# knxhome-lqfp32-v3.net
KiCad netlist of a schematic drawn in EAGLE
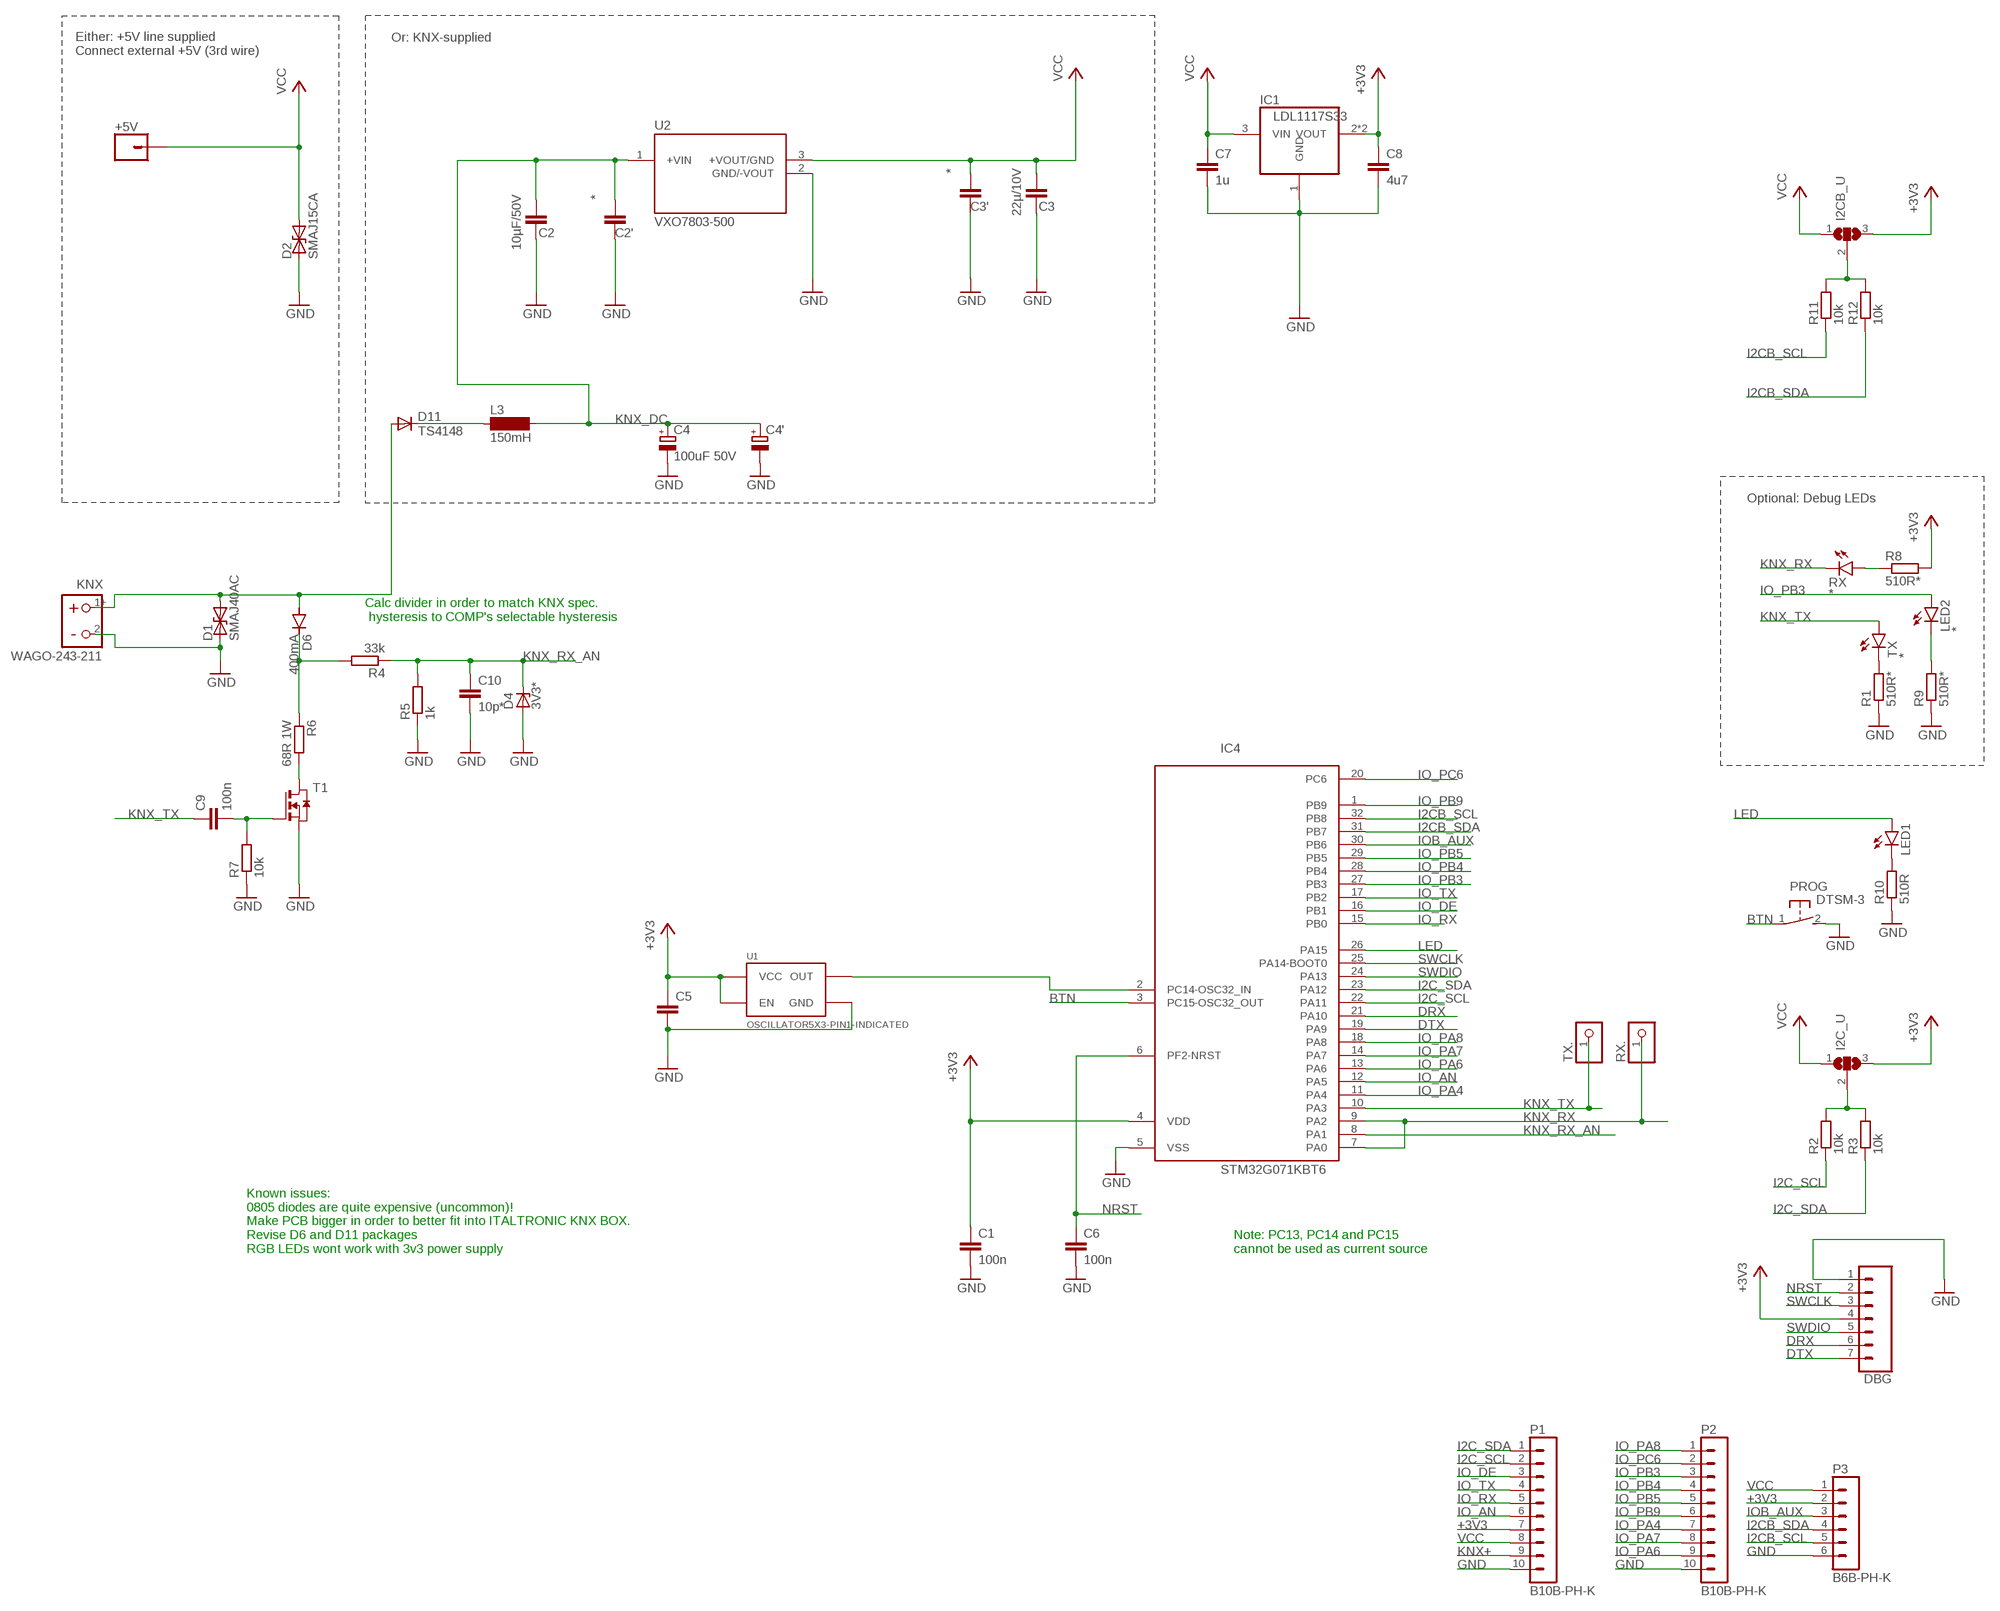
[diagram p0: schematic, sheet 1]

(export (version "E")
  (design (tool "Eeschema 10.0.6"))
  (components
    (comp (ref "+5V")
      (value "CONN_01PTH_LONGPAD")
      (footprint "eagle-import:1X01_LONGPAD")
      (libsource (lib "eagle-import") (part "CONN_01PTH_LONGPAD"))
    )
    (comp (ref "C1")
      (value "100n")
      (footprint "eagle-import:C0805")
      (libsource (lib "eagle-import") (part "C-EUC0805"))
    )
    (comp (ref "C2")
      (value "10µF/50V")
      (footprint "eagle-import:C1210")
      (libsource (lib "eagle-import") (part "C-EUC1210"))
    )
    (comp (ref "C2'")
      (value "*")
      (footprint "eagle-import:C1210")
      (libsource (lib "eagle-import") (part "C-EUC1210"))
    )
    (comp (ref "C3")
      (value "22µ/10V")
      (footprint "eagle-import:C1210")
      (libsource (lib "eagle-import") (part "C-EUC1210"))
    )
    (comp (ref "C3'")
      (value "*")
      (footprint "eagle-import:C1210")
      (libsource (lib "eagle-import") (part "C-EUC1210"))
    )
    (comp (ref "C4")
      (value "100uF 50V")
      (footprint "eagle-import:E3,5-8")
      (libsource (lib "eagle-import") (part "CPOL-EUE3.5-8"))
    )
    (comp (ref "C4'")
      (value "CPOL-EU153CLV-0810")
      (footprint "eagle-import:153CLV-0810")
      (libsource (lib "eagle-import") (part "resistor_348_CPOL-EU153CLV-0810"))
    )
    (comp (ref "C5")
      (value "C-EUC0805")
      (footprint "eagle-import:C0805")
      (libsource (lib "eagle-import") (part "C-EUC0805"))
    )
    (comp (ref "C6")
      (value "100n")
      (footprint "eagle-import:C0805")
      (libsource (lib "eagle-import") (part "C-EUC0805"))
    )
    (comp (ref "C7")
      (value "1u")
      (footprint "eagle-import:C0805")
      (libsource (lib "eagle-import") (part "C-EUC0805"))
    )
    (comp (ref "C8")
      (value "4u7")
      (footprint "eagle-import:C0805")
      (libsource (lib "eagle-import") (part "C-EUC0805"))
    )
    (comp (ref "C9")
      (value "100n")
      (footprint "eagle-import:C0805")
      (libsource (lib "eagle-import") (part "C-EUC0805"))
    )
    (comp (ref "C10")
      (value "10p*")
      (footprint "eagle-import:C0805")
      (libsource (lib "eagle-import") (part "C-EUC0805"))
    )
    (comp (ref "D1")
      (value "SMAJ40AC")
      (footprint "eagle-import:DO-214AC")
      (libsource (lib "eagle-import") (part "SMAJ40AC"))
    )
    (comp (ref "D2")
      (value "SMAJ15CA")
      (footprint "eagle-import:DO-214AC")
      (libsource (lib "eagle-import") (part "SMAJ40AC"))
    )
    (comp (ref "D4")
      (value "3V3*")
      (footprint "eagle-import:SOT23")
      (libsource (lib "eagle-import") (part "ZENER-DIODESOT23"))
    )
    (comp (ref "D6")
      (value "400mA")
      (footprint "eagle-import:SOD123")
      (libsource (lib "eagle-import") (part "diode_210_DIODE-SOD123"))
    )
    (comp (ref "D11")
      (value "TS4148")
      (footprint "eagle-import:SOD123")
      (libsource (lib "eagle-import") (part "DIODE-SOD123"))
    )
    (comp (ref "DBG")
      (value "CONN_07LOCK")
      (footprint "eagle-import:1X07_LOCK")
      (libsource (lib "eagle-import") (part "CONN_07LOCK"))
    )
    (comp (ref "I2CB_U")
      (value "SJ2W")
      (footprint "eagle-import:SJ_2")
      (libsource (lib "eagle-import") (part "SJ2W"))
    )
    (comp (ref "I2C_U")
      (value "SJ2W")
      (footprint "eagle-import:SJ_2")
      (libsource (lib "eagle-import") (part "SJ2W"))
    )
    (comp (ref "IC1")
      (value "LDL1117S33")
      (footprint "eagle-import:SOT223")
      (fields (field (name "MPN") "REG1117"))
      (libsource (lib "eagle-import") (part "REG1117"))
    )
    (comp (ref "IC4")
      (value "STM32G071KBT6")
      (footprint "eagle-import:LQFP32")
      (libsource (lib "eagle-import") (part "STM32G071KBT6"))
    )
    (comp (ref "KNX")
      (value "WAGO-243-211")
      (footprint "eagle-import:WAGO-243-211")
      (libsource (lib "eagle-import") (part "WAGO-243-211"))
    )
    (comp (ref "L3")
      (value "150mH")
      (footprint "eagle-import:BS11_LIEGEND")
      (libsource (lib "eagle-import") (part "SD12BS11_LIEGEND"))
    )
    (comp (ref "LED1")
      (value "LEDCHIPLED_1206")
      (footprint "eagle-import:CHIPLED_1206")
      (libsource (lib "eagle-import") (part "LEDCHIPLED_1206"))
    )
    (comp (ref "LED2")
      (value "*")
      (footprint "eagle-import:CHIPLED_1206")
      (libsource (lib "eagle-import") (part "LEDCHIPLED_1206"))
    )
    (comp (ref "P1")
      (value "B10B-PH-K")
      (footprint "eagle-import:B10B-PH-K")
      (libsource (lib "eagle-import") (part "B10B-PH-K"))
    )
    (comp (ref "P2")
      (value "B10B-PH-K")
      (footprint "eagle-import:B10B-PH-K")
      (libsource (lib "eagle-import") (part "B10B-PH-K"))
    )
    (comp (ref "P3")
      (value "B6B-PH-K")
      (footprint "eagle-import:B6B-PH-K")
      (libsource (lib "eagle-import") (part "B6B-PH-K"))
    )
    (comp (ref "PROG")
      (value "DTSM-3")
      (footprint "eagle-import:DTSM-3")
      (libsource (lib "eagle-import") (part "DTSM-3"))
    )
    (comp (ref "R1")
      (value "510R*")
      (footprint "eagle-import:R0805")
      (libsource (lib "eagle-import") (part "R-EU_R0805"))
    )
    (comp (ref "R2")
      (value "10k")
      (footprint "eagle-import:R0805")
      (libsource (lib "eagle-import") (part "R-EU_R0805"))
    )
    (comp (ref "R3")
      (value "10k")
      (footprint "eagle-import:R0805")
      (libsource (lib "eagle-import") (part "R-EU_R0805"))
    )
    (comp (ref "R4")
      (value "33k")
      (footprint "eagle-import:R0805")
      (libsource (lib "eagle-import") (part "R-EU_R0805"))
    )
    (comp (ref "R5")
      (value "1k")
      (footprint "eagle-import:R0805")
      (libsource (lib "eagle-import") (part "R-EU_R0805"))
    )
    (comp (ref "R6")
      (value "68R 1W")
      (footprint "eagle-import:R2512")
      (libsource (lib "eagle-import") (part "R-EU_R2512"))
    )
    (comp (ref "R7")
      (value "10k")
      (footprint "eagle-import:R0805")
      (libsource (lib "eagle-import") (part "R-EU_R0805"))
    )
    (comp (ref "R8")
      (value "510R*")
      (footprint "eagle-import:R0805")
      (libsource (lib "eagle-import") (part "R-EU_R0805"))
    )
    (comp (ref "R9")
      (value "510R*")
      (footprint "eagle-import:R0805")
      (libsource (lib "eagle-import") (part "R-EU_R0805"))
    )
    (comp (ref "R10")
      (value "510R")
      (footprint "eagle-import:R0805")
      (libsource (lib "eagle-import") (part "R-EU_R0805"))
    )
    (comp (ref "R11")
      (value "10k")
      (footprint "eagle-import:R0805")
      (libsource (lib "eagle-import") (part "R-EU_R0805"))
    )
    (comp (ref "R12")
      (value "10k")
      (footprint "eagle-import:R0805")
      (libsource (lib "eagle-import") (part "R-EU_R0805"))
    )
    (comp (ref "RX")
      (value "*")
      (footprint "eagle-import:CHIPLED_1206")
      (libsource (lib "eagle-import") (part "LEDCHIPLED_1206"))
    )
    (comp (ref "RX.")
      (value "PINHD-1X1")
      (footprint "eagle-import:1X01")
      (libsource (lib "eagle-import") (part "PINHD-1X1"))
    )
    (comp (ref "T1")
      (value "NMOSSOT23")
      (footprint "eagle-import:SOT-23")
      (libsource (lib "eagle-import") (part "NMOSSOT23"))
    )
    (comp (ref "TX")
      (value "*")
      (footprint "eagle-import:CHIPLED_1206")
      (libsource (lib "eagle-import") (part "LEDCHIPLED_1206"))
    )
    (comp (ref "TX.")
      (value "PINHD-1X1")
      (footprint "eagle-import:1X01")
      (libsource (lib "eagle-import") (part "PINHD-1X1"))
    )
    (comp (ref "U1")
      (value "OSCILLATOR5X3-PIN1-INDICATED")
      (footprint "eagle-import:CRYSTAL-OSC-SMD-5X3")
      (libsource (lib "eagle-import") (part "OSCILLATOR5X3-PIN1-INDICATED"))
    )
    (comp (ref "U2")
      (value "VXO7803-500")
      (footprint "eagle-import:CONV_VXO7803-500")
      (fields (field (name "MANUFACTURER") "CUI Inc"))
      (libsource (lib "eagle-import") (part "VXO7803-500"))
    )
  )
  (nets
    (net (code "1") (name "+3V3") (class "Default")
      (node (ref "C1") (pin "1") (pinfunction "1_1") (pintype "passive"))
      (node (ref "C5") (pin "1") (pinfunction "1_1") (pintype "passive"))
      (node (ref "C8") (pin "1") (pinfunction "1_1") (pintype "passive"))
      (node (ref "DBG") (pin "4") (pinfunction "4_4") (pintype "passive"))
      (node (ref "I2CB_U") (pin "3") (pinfunction "3_3") (pintype "passive"))
      (node (ref "I2C_U") (pin "3") (pinfunction "3_3") (pintype "passive"))
      (node (ref "IC1") (pin "2") (pinfunction "VOUT_2") (pintype "output"))
      (node (ref "IC1") (pin "4") (pinfunction "VOUT_4") (pintype "output"))
      (node (ref "IC4") (pin "4") (pinfunction "VDD_4") (pintype "power_in"))
      (node (ref "P1") (pin "7") (pinfunction "7_7") (pintype "passive"))
      (node (ref "P3") (pin "2") (pinfunction "2_2") (pintype "passive"))
      (node (ref "R8") (pin "2") (pinfunction "2_2") (pintype "passive"))
      (node (ref "U1") (pin "1") (pinfunction "EN_1") (pintype "bidirectional"))
      (node (ref "U1") (pin "4") (pinfunction "VCC_4") (pintype "bidirectional"))
    )
    (net (code "2") (name "/BTN") (class "Default")
      (node (ref "IC4") (pin "3") (pinfunction "PC15-OSC32_OUT_3") (pintype "bidirectional"))
      (node (ref "PROG") (pin "1") (pinfunction "1_1") (pintype "passive"))
    )
    (net (code "3") (name "/DRX") (class "Default")
      (node (ref "DBG") (pin "6") (pinfunction "6_6") (pintype "passive"))
      (node (ref "IC4") (pin "21") (pinfunction "PA10_21") (pintype "bidirectional"))
    )
    (net (code "4") (name "/DTX") (class "Default")
      (node (ref "DBG") (pin "7") (pinfunction "7_7") (pintype "passive"))
      (node (ref "IC4") (pin "19") (pinfunction "PA9_19") (pintype "bidirectional"))
    )
    (net (code "5") (name "/I2CB_SCL") (class "Default")
      (node (ref "IC4") (pin "32") (pinfunction "PB8_32") (pintype "bidirectional"))
      (node (ref "P3") (pin "5") (pinfunction "5_5") (pintype "passive"))
      (node (ref "R11") (pin "1") (pinfunction "1_1") (pintype "passive"))
    )
    (net (code "6") (name "/I2CB_SDA") (class "Default")
      (node (ref "IC4") (pin "31") (pinfunction "PB7_31") (pintype "bidirectional"))
      (node (ref "P3") (pin "4") (pinfunction "4_4") (pintype "passive"))
      (node (ref "R12") (pin "1") (pinfunction "1_1") (pintype "passive"))
    )
    (net (code "7") (name "/I2C_SCL") (class "Default")
      (node (ref "IC4") (pin "22") (pinfunction "PA11_22") (pintype "bidirectional"))
      (node (ref "P1") (pin "2") (pinfunction "2_2") (pintype "passive"))
      (node (ref "R2") (pin "1") (pinfunction "1_1") (pintype "passive"))
    )
    (net (code "8") (name "/I2C_SDA") (class "Default")
      (node (ref "IC4") (pin "23") (pinfunction "PA12_23") (pintype "bidirectional"))
      (node (ref "P1") (pin "1") (pinfunction "1_1") (pintype "passive"))
      (node (ref "R3") (pin "1") (pinfunction "1_1") (pintype "passive"))
    )
    (net (code "9") (name "/IOB_AUX") (class "Default")
      (node (ref "IC4") (pin "30") (pinfunction "PB6_30") (pintype "bidirectional"))
      (node (ref "P3") (pin "3") (pinfunction "3_3") (pintype "passive"))
    )
    (net (code "10") (name "/IO_AN") (class "Default")
      (node (ref "IC4") (pin "12") (pinfunction "PA5_12") (pintype "bidirectional"))
      (node (ref "P1") (pin "6") (pinfunction "6_6") (pintype "passive"))
    )
    (net (code "11") (name "/IO_DE") (class "Default")
      (node (ref "IC4") (pin "16") (pinfunction "PB1_16") (pintype "bidirectional"))
      (node (ref "P1") (pin "3") (pinfunction "3_3") (pintype "passive"))
    )
    (net (code "12") (name "/IO_PA4") (class "Default")
      (node (ref "IC4") (pin "11") (pinfunction "PA4_11") (pintype "bidirectional"))
      (node (ref "P2") (pin "7") (pinfunction "7_7") (pintype "passive"))
    )
    (net (code "13") (name "/IO_PA6") (class "Default")
      (node (ref "IC4") (pin "13") (pinfunction "PA6_13") (pintype "bidirectional"))
      (node (ref "P2") (pin "9") (pinfunction "9_9") (pintype "passive"))
    )
    (net (code "14") (name "/IO_PA7") (class "Default")
      (node (ref "IC4") (pin "14") (pinfunction "PA7_14") (pintype "bidirectional"))
      (node (ref "P2") (pin "8") (pinfunction "8_8") (pintype "passive"))
    )
    (net (code "15") (name "/IO_PA8") (class "Default")
      (node (ref "IC4") (pin "18") (pinfunction "PA8_18") (pintype "bidirectional"))
      (node (ref "P2") (pin "1") (pinfunction "1_1") (pintype "passive"))
    )
    (net (code "16") (name "/IO_PB3") (class "Default")
      (node (ref "IC4") (pin "27") (pinfunction "PB3_27") (pintype "bidirectional"))
      (node (ref "LED2") (pin "A") (pinfunction "A_A") (pintype "passive"))
      (node (ref "P2") (pin "3") (pinfunction "3_3") (pintype "passive"))
    )
    (net (code "17") (name "/IO_PB4") (class "Default")
      (node (ref "IC4") (pin "28") (pinfunction "PB4_28") (pintype "bidirectional"))
      (node (ref "P2") (pin "4") (pinfunction "4_4") (pintype "passive"))
    )
    (net (code "18") (name "/IO_PB5") (class "Default")
      (node (ref "IC4") (pin "29") (pinfunction "PB5_29") (pintype "bidirectional"))
      (node (ref "P2") (pin "5") (pinfunction "5_5") (pintype "passive"))
    )
    (net (code "19") (name "/IO_PB9") (class "Default")
      (node (ref "IC4") (pin "1") (pinfunction "PB9_1") (pintype "bidirectional"))
      (node (ref "P2") (pin "6") (pinfunction "6_6") (pintype "passive"))
    )
    (net (code "20") (name "/IO_PC6") (class "Default")
      (node (ref "IC4") (pin "20") (pinfunction "PC6_20") (pintype "bidirectional"))
      (node (ref "P2") (pin "2") (pinfunction "2_2") (pintype "passive"))
    )
    (net (code "21") (name "/IO_RX") (class "Default")
      (node (ref "IC4") (pin "15") (pinfunction "PB0_15") (pintype "bidirectional"))
      (node (ref "P1") (pin "5") (pinfunction "5_5") (pintype "passive"))
    )
    (net (code "22") (name "/IO_TX") (class "Default")
      (node (ref "IC4") (pin "17") (pinfunction "PB2_17") (pintype "bidirectional"))
      (node (ref "P1") (pin "4") (pinfunction "4_4") (pintype "passive"))
    )
    (net (code "23") (name "/KNX+") (class "Default")
      (node (ref "D1") (pin "C") (pinfunction "C_C") (pintype "passive"))
      (node (ref "D11") (pin "A") (pinfunction "A_A") (pintype "passive"))
      (node (ref "D6") (pin "A") (pinfunction "A_A") (pintype "passive"))
      (node (ref "KNX") (pin "1+") (pinfunction "1+_1+") (pintype "passive"))
      (node (ref "P1") (pin "9") (pinfunction "9_9") (pintype "passive"))
    )
    (net (code "24") (name "/KNX_DC") (class "Default")
      (node (ref "C2") (pin "2") (pinfunction "2_2") (pintype "passive"))
      (node (ref "C2'") (pin "2") (pinfunction "2_2") (pintype "passive"))
      (node (ref "C4") (pin "+") (pinfunction "+_+") (pintype "passive"))
      (node (ref "C4'") (pin "+") (pinfunction "+_+") (pintype "passive"))
      (node (ref "L3") (pin "2") (pinfunction "2_2") (pintype "passive"))
      (node (ref "U2") (pin "1") (pinfunction "+VIN_1") (pintype "input"))
    )
    (net (code "25") (name "/KNX_RX") (class "Default")
      (node (ref "IC4") (pin "7") (pinfunction "PA0_7") (pintype "bidirectional"))
      (node (ref "IC4") (pin "9") (pinfunction "PA2_9") (pintype "bidirectional"))
      (node (ref "RX") (pin "C") (pinfunction "C_C") (pintype "passive"))
      (node (ref "RX.") (pin "1") (pinfunction "1_1") (pintype "passive"))
    )
    (net (code "26") (name "/KNX_RX_AN") (class "Default")
      (node (ref "C10") (pin "1") (pinfunction "1_1") (pintype "passive"))
      (node (ref "D4") (pin "3") (pinfunction "C_3") (pintype "passive"))
      (node (ref "IC4") (pin "8") (pinfunction "PA1_8") (pintype "bidirectional"))
      (node (ref "R4") (pin "1") (pinfunction "1_1") (pintype "passive"))
      (node (ref "R5") (pin "2") (pinfunction "2_2") (pintype "passive"))
    )
    (net (code "27") (name "/KNX_TX") (class "Default")
      (node (ref "C9") (pin "1") (pinfunction "1_1") (pintype "passive"))
      (node (ref "IC4") (pin "10") (pinfunction "PA3_10") (pintype "bidirectional"))
      (node (ref "TX") (pin "A") (pinfunction "A_A") (pintype "passive"))
      (node (ref "TX.") (pin "1") (pinfunction "1_1") (pintype "passive"))
    )
    (net (code "28") (name "/LED") (class "Default")
      (node (ref "IC4") (pin "26") (pinfunction "PA15_26") (pintype "bidirectional"))
      (node (ref "LED1") (pin "A") (pinfunction "A_A") (pintype "passive"))
    )
    (net (code "29") (name "/NRST") (class "Default")
      (node (ref "C6") (pin "1") (pinfunction "1_1") (pintype "passive"))
      (node (ref "DBG") (pin "2") (pinfunction "2_2") (pintype "passive"))
      (node (ref "IC4") (pin "6") (pinfunction "PF2-NRST_6") (pintype "bidirectional"))
    )
    (net (code "30") (name "/SWCLK") (class "Default")
      (node (ref "DBG") (pin "3") (pinfunction "3_3") (pintype "passive"))
      (node (ref "IC4") (pin "25") (pinfunction "PA14-BOOT0_25") (pintype "bidirectional"))
    )
    (net (code "31") (name "/SWDIO") (class "Default")
      (node (ref "DBG") (pin "5") (pinfunction "5_5") (pintype "passive"))
      (node (ref "IC4") (pin "24") (pinfunction "PA13_24") (pintype "bidirectional"))
    )
    (net (code "32") (name "GND") (class "Default")
      (node (ref "C1") (pin "2") (pinfunction "2_2") (pintype "passive"))
      (node (ref "C10") (pin "2") (pinfunction "2_2") (pintype "passive"))
      (node (ref "C2") (pin "1") (pinfunction "1_1") (pintype "passive"))
      (node (ref "C2'") (pin "1") (pinfunction "1_1") (pintype "passive"))
      (node (ref "C3") (pin "1") (pinfunction "1_1") (pintype "passive"))
      (node (ref "C3'") (pin "1") (pinfunction "1_1") (pintype "passive"))
      (node (ref "C4") (pin "-") (pinfunction "-_-") (pintype "passive"))
      (node (ref "C4'") (pin "-") (pinfunction "-_-") (pintype "passive"))
      (node (ref "C5") (pin "2") (pinfunction "2_2") (pintype "passive"))
      (node (ref "C6") (pin "2") (pinfunction "2_2") (pintype "passive"))
      (node (ref "C7") (pin "2") (pinfunction "2_2") (pintype "passive"))
      (node (ref "C8") (pin "2") (pinfunction "2_2") (pintype "passive"))
      (node (ref "D1") (pin "A") (pinfunction "A_A") (pintype "passive"))
      (node (ref "D2") (pin "A") (pinfunction "A_A") (pintype "passive"))
      (node (ref "D4") (pin "1") (pinfunction "A_1") (pintype "passive"))
      (node (ref "DBG") (pin "1") (pinfunction "1_1") (pintype "passive"))
      (node (ref "IC1") (pin "1") (pinfunction "GND_1") (pintype "power_in"))
      (node (ref "IC4") (pin "5") (pinfunction "VSS_5") (pintype "power_in"))
      (node (ref "KNX") (pin "2-") (pinfunction "2-_2-") (pintype "passive"))
      (node (ref "P1") (pin "10") (pinfunction "10_10") (pintype "passive"))
      (node (ref "P2") (pin "10") (pinfunction "10_10") (pintype "passive"))
      (node (ref "P3") (pin "6") (pinfunction "6_6") (pintype "passive"))
      (node (ref "PROG") (pin "2") (pinfunction "2_2") (pintype "passive"))
      (node (ref "R1") (pin "1") (pinfunction "1_1") (pintype "passive"))
      (node (ref "R10") (pin "1") (pinfunction "1_1") (pintype "passive"))
      (node (ref "R5") (pin "1") (pinfunction "1_1") (pintype "passive"))
      (node (ref "R7") (pin "1") (pinfunction "1_1") (pintype "passive"))
      (node (ref "R9") (pin "1") (pinfunction "1_1") (pintype "passive"))
      (node (ref "T1") (pin "2") (pinfunction "S_2") (pintype "passive"))
      (node (ref "U1") (pin "2") (pinfunction "GND_2") (pintype "bidirectional"))
      (node (ref "U2") (pin "2") (pinfunction "GND/-VOUT_2") (pintype "output"))
    )
    (net (code "33") (name "Net-(D6-PadC)") (class "Default")
      (node (ref "D6") (pin "C") (pinfunction "C_C") (pintype "passive"))
      (node (ref "R4") (pin "2") (pinfunction "2_2") (pintype "passive"))
      (node (ref "R6") (pin "1") (pinfunction "1_1") (pintype "passive"))
    )
    (net (code "34") (name "Net-(D11-PadC)") (class "Default")
      (node (ref "D11") (pin "C") (pinfunction "C_C") (pintype "passive"))
      (node (ref "L3") (pin "1") (pinfunction "1_1") (pintype "passive"))
    )
    (net (code "35") (name "Net-(I2CB_U-Pad2)") (class "Default")
      (node (ref "I2CB_U") (pin "2") (pinfunction "2_2") (pintype "passive"))
      (node (ref "R11") (pin "2") (pinfunction "2_2") (pintype "passive"))
      (node (ref "R12") (pin "2") (pinfunction "2_2") (pintype "passive"))
    )
    (net (code "36") (name "Net-(I2C_U-Pad2)") (class "Default")
      (node (ref "I2C_U") (pin "2") (pinfunction "2_2") (pintype "passive"))
      (node (ref "R2") (pin "2") (pinfunction "2_2") (pintype "passive"))
      (node (ref "R3") (pin "2") (pinfunction "2_2") (pintype "passive"))
    )
    (net (code "37") (name "Net-(IC4-PC14-OSC32_IN)") (class "Default")
      (node (ref "IC4") (pin "2") (pinfunction "PC14-OSC32_IN_2") (pintype "bidirectional"))
      (node (ref "U1") (pin "3") (pinfunction "OUT_3") (pintype "bidirectional"))
    )
    (net (code "38") (name "Net-(LED1-PadC)") (class "Default")
      (node (ref "LED1") (pin "C") (pinfunction "C_C") (pintype "passive"))
      (node (ref "R10") (pin "2") (pinfunction "2_2") (pintype "passive"))
    )
    (net (code "39") (name "Net-(LED2-PadC)") (class "Default")
      (node (ref "LED2") (pin "C") (pinfunction "C_C") (pintype "passive"))
      (node (ref "R9") (pin "2") (pinfunction "2_2") (pintype "passive"))
    )
    (net (code "40") (name "Net-(R1-Pad2)") (class "Default")
      (node (ref "R1") (pin "2") (pinfunction "2_2") (pintype "passive"))
      (node (ref "TX") (pin "C") (pinfunction "C_C") (pintype "passive"))
    )
    (net (code "41") (name "Net-(R8-Pad1)") (class "Default")
      (node (ref "R8") (pin "1") (pinfunction "1_1") (pintype "passive"))
      (node (ref "RX") (pin "A") (pinfunction "A_A") (pintype "passive"))
    )
    (net (code "42") (name "Net-(T1-D)") (class "Default")
      (node (ref "R6") (pin "2") (pinfunction "2_2") (pintype "passive"))
      (node (ref "T1") (pin "1") (pinfunction "D_1") (pintype "passive"))
    )
    (net (code "43") (name "Net-(T1-G)") (class "Default")
      (node (ref "C9") (pin "2") (pinfunction "2_2") (pintype "passive"))
      (node (ref "R7") (pin "2") (pinfunction "2_2") (pintype "passive"))
      (node (ref "T1") (pin "3") (pinfunction "G_3") (pintype "passive"))
    )
    (net (code "44") (name "VCC") (class "Default")
      (node (ref "+5V") (pin "1") (pinfunction "1_1") (pintype "passive"))
      (node (ref "C3") (pin "2") (pinfunction "2_2") (pintype "passive"))
      (node (ref "C3'") (pin "2") (pinfunction "2_2") (pintype "passive"))
      (node (ref "C7") (pin "1") (pinfunction "1_1") (pintype "passive"))
      (node (ref "D2") (pin "C") (pinfunction "C_C") (pintype "passive"))
      (node (ref "I2CB_U") (pin "1") (pinfunction "1_1") (pintype "passive"))
      (node (ref "I2C_U") (pin "1") (pinfunction "1_1") (pintype "passive"))
      (node (ref "IC1") (pin "3") (pinfunction "VIN_3") (pintype "input"))
      (node (ref "P1") (pin "8") (pinfunction "8_8") (pintype "passive"))
      (node (ref "P3") (pin "1") (pinfunction "1_1") (pintype "passive"))
      (node (ref "U2") (pin "3") (pinfunction "+VOUT/GND_3") (pintype "output"))
    )
  )
)
